# chaprintesting13viasmichael.net
KiCad netlist of a schematic drawn in EAGLE
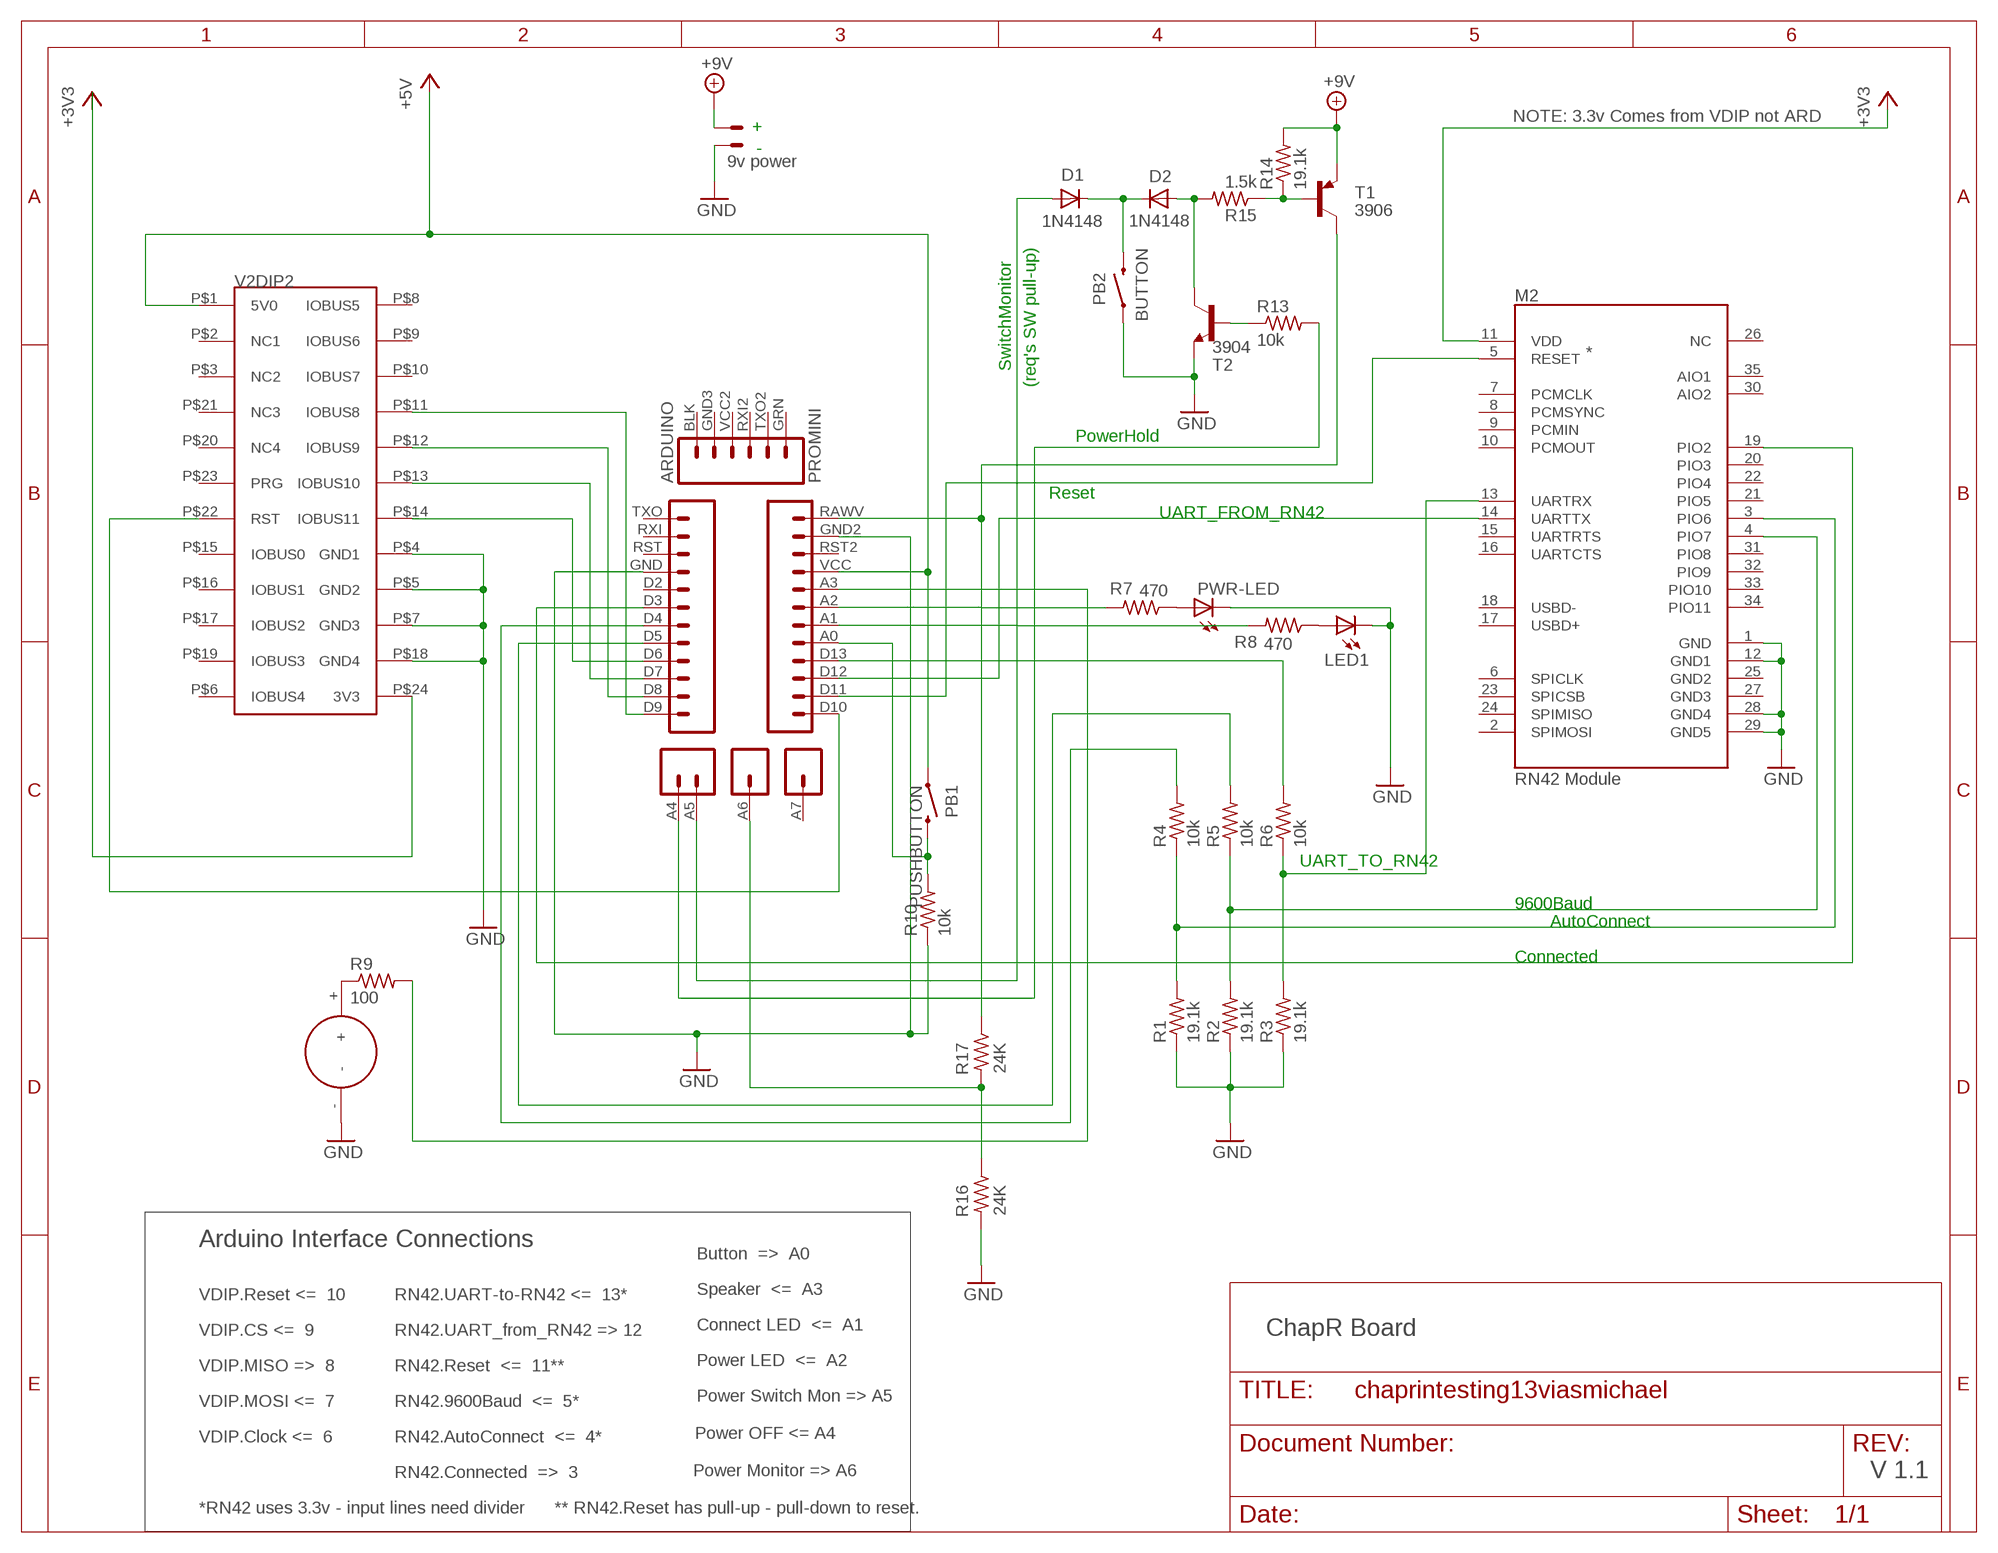
[diagram p0: schematic, sheet 1]

(export (version "E")
  (design (tool "Eeschema 10.0.6"))
  (components
    (comp (ref "-")
      (value "9v power")
      (footprint "eagle-import:22-23-2021")
      (fields (field (name "MF") "MOLEX") (field (name "MPN") "22-23-2021"))
      (libsource (lib "eagle-import") (part "22-23-2021"))
    )
    (comp (ref "ARDUINO")
      (value "PROMINI")
      (footprint "eagle-import:PROMINI")
      (libsource (lib "eagle-import") (part "PROMINI"))
    )
    (comp (ref "D1")
      (value "1N4148")
      (footprint "eagle-import:DO35-7")
      (libsource (lib "eagle-import") (part "1N4148DO35-7"))
    )
    (comp (ref "D2")
      (value "1N4148")
      (footprint "eagle-import:DO35-7")
      (libsource (lib "eagle-import") (part "1N4148DO35-7"))
    )
    (comp (ref "LED1")
      (value "LED3MM")
      (footprint "eagle-import:LED3MM")
      (libsource (lib "eagle-import") (part "LED3MM"))
    )
    (comp (ref "M2")
      (value "RN42 Module")
      (footprint "eagle-import:RN41")
      (libsource (lib "eagle-import") (part "BLUETOOTH-RN41{dblquote}"))
    )
    (comp (ref "PB1")
      (value "PUSHBUTTON")
      (footprint "eagle-import:2-PIN-PUSHBUTTON")
      (libsource (lib "eagle-import") (part "PUSHBUTTON"))
    )
    (comp (ref "PB2")
      (value "BUTTON")
      (footprint "eagle-import:2-PIN-PUSHBUTTON")
      (libsource (lib "eagle-import") (part "PUSHBUTTON"))
    )
    (comp (ref "PWR-LED")
      (value "LED3MM")
      (footprint "eagle-import:LED3MM")
      (libsource (lib "eagle-import") (part "LED3MM"))
    )
    (comp (ref "R1")
      (value "19.1k")
      (footprint "eagle-import:0207_10")
      (libsource (lib "eagle-import") (part "R-US_0207/10"))
    )
    (comp (ref "R2")
      (value "19.1k")
      (footprint "eagle-import:0207_10")
      (libsource (lib "eagle-import") (part "R-US_0207/10"))
    )
    (comp (ref "R3")
      (value "19.1k")
      (footprint "eagle-import:0207_10")
      (libsource (lib "eagle-import") (part "R-US_0207/10"))
    )
    (comp (ref "R4")
      (value "10k")
      (footprint "eagle-import:0207_10")
      (libsource (lib "eagle-import") (part "R-US_0207/10"))
    )
    (comp (ref "R5")
      (value "10k")
      (footprint "eagle-import:0207_10")
      (libsource (lib "eagle-import") (part "R-US_0207/10"))
    )
    (comp (ref "R6")
      (value "10k")
      (footprint "eagle-import:0207_10")
      (libsource (lib "eagle-import") (part "R-US_0207/10"))
    )
    (comp (ref "R7")
      (value "470")
      (footprint "eagle-import:0207_10")
      (libsource (lib "eagle-import") (part "R-US_0207/10"))
    )
    (comp (ref "R8")
      (value "470")
      (footprint "eagle-import:0207_10")
      (libsource (lib "eagle-import") (part "R-US_0207/10"))
    )
    (comp (ref "R9")
      (value "100")
      (footprint "eagle-import:0207_10")
      (libsource (lib "eagle-import") (part "R-US_0207/10"))
    )
    (comp (ref "R10")
      (value "10k")
      (footprint "eagle-import:0207_10")
      (libsource (lib "eagle-import") (part "R-US_0207/10"))
    )
    (comp (ref "R13")
      (value "10k")
      (footprint "eagle-import:0207_10")
      (libsource (lib "eagle-import") (part "R-US_0207/10"))
    )
    (comp (ref "R14")
      (value "19.1k")
      (footprint "eagle-import:0207_10")
      (libsource (lib "eagle-import") (part "R-US_0207/10"))
    )
    (comp (ref "R15")
      (value "1.5k")
      (footprint "eagle-import:0207_10")
      (libsource (lib "eagle-import") (part "R-US_0207/10"))
    )
    (comp (ref "R16")
      (value "24K")
      (footprint "eagle-import:0207_10")
      (libsource (lib "eagle-import") (part "R-US_0207/10"))
    )
    (comp (ref "R17")
      (value "24K")
      (footprint "eagle-import:0207_10")
      (libsource (lib "eagle-import") (part "R-US_0207/10"))
    )
    (comp (ref "T1")
      (value "3906")
      (footprint "eagle-import:TO92-EBC")
      (libsource (lib "eagle-import") (part "-PNP-TO92-EBC"))
    )
    (comp (ref "T2")
      (value "3904")
      (footprint "eagle-import:TO92-EBC")
      (libsource (lib "eagle-import") (part "-NPN-TO92-EBC"))
    )
    (comp (ref "U$2")
      (value "SPEAKER")
      (footprint "eagle-import:SPEAKER")
      (libsource (lib "eagle-import") (part "SPEAKER"))
    )
    (comp (ref "V2DIP2")
      (value "V2DIP2")
      (footprint "eagle-import:V2DIP2")
      (libsource (lib "eagle-import") (part "V2DIP2"))
    )
  )
  (nets
    (net (code "1") (name "+3V3") (class "Default")
      (node (ref "M2") (pin "11") (pinfunction "VDD_11") (pintype "bidirectional"))
    )
    (net (code "2") (name "+5V") (class "Default")
      (node (ref "ARDUINO") (pin "VCC") (pinfunction "VCC_VCC") (pintype "passive"))
      (node (ref "PB1") (pin "P$1") (pinfunction "1_P$1") (pintype "passive"))
      (node (ref "V2DIP2") (pin "P$1") (pinfunction "5V0_P$1") (pintype "bidirectional"))
    )
    (net (code "3") (name "+9V") (class "Default")
      (node (ref "-") (pin "2") (pinfunction "S_2") (pintype "passive"))
      (node (ref "R14") (pin "2") (pinfunction "2_2") (pintype "passive"))
      (node (ref "T1") (pin "E") (pinfunction "E_E") (pintype "passive"))
    )
    (net (code "4") (name "GND") (class "Default")
      (node (ref "-") (pin "1") (pinfunction "S_1") (pintype "passive"))
      (node (ref "ARDUINO") (pin "GND") (pinfunction "GND_GND") (pintype "passive"))
      (node (ref "ARDUINO") (pin "GND2") (pinfunction "GND2_GND2") (pintype "passive"))
      (node (ref "LED1") (pin "K") (pinfunction "C_K") (pintype "passive"))
      (node (ref "M2") (pin "1") (pinfunction "GND_1") (pintype "bidirectional"))
      (node (ref "M2") (pin "12") (pinfunction "GND1_12") (pintype "bidirectional"))
      (node (ref "M2") (pin "28") (pinfunction "GND4_28") (pintype "bidirectional"))
      (node (ref "M2") (pin "29") (pinfunction "GND5_29") (pintype "bidirectional"))
      (node (ref "PB2") (pin "P$1") (pinfunction "1_P$1") (pintype "passive"))
      (node (ref "PWR-LED") (pin "K") (pinfunction "C_K") (pintype "passive"))
      (node (ref "R1") (pin "1") (pinfunction "1_1") (pintype "passive"))
      (node (ref "R10") (pin "1") (pinfunction "1_1") (pintype "passive"))
      (node (ref "R16") (pin "2") (pinfunction "2_2") (pintype "passive"))
      (node (ref "R2") (pin "1") (pinfunction "1_1") (pintype "passive"))
      (node (ref "R3") (pin "1") (pinfunction "1_1") (pintype "passive"))
      (node (ref "T2") (pin "E") (pinfunction "E_E") (pintype "passive"))
      (node (ref "U$2") (pin "-") (pinfunction "-_-") (pintype "bidirectional"))
      (node (ref "V2DIP2") (pin "P$18") (pinfunction "GND4_P$18") (pintype "bidirectional"))
      (node (ref "V2DIP2") (pin "P$4") (pinfunction "GND1_P$4") (pintype "bidirectional"))
      (node (ref "V2DIP2") (pin "P$5") (pinfunction "GND2_P$5") (pintype "bidirectional"))
      (node (ref "V2DIP2") (pin "P$7") (pinfunction "GND3_P$7") (pintype "bidirectional"))
    )
    (net (code "5") (name "Net-(ARDUINO-PadA1)") (class "Default")
      (node (ref "ARDUINO") (pin "A1") (pinfunction "A1_A1") (pintype "passive"))
      (node (ref "R8") (pin "2") (pinfunction "2_2") (pintype "passive"))
    )
    (net (code "6") (name "Net-(ARDUINO-PadA2)") (class "Default")
      (node (ref "ARDUINO") (pin "A2") (pinfunction "A2_A2") (pintype "passive"))
      (node (ref "R7") (pin "2") (pinfunction "2_2") (pintype "passive"))
    )
    (net (code "7") (name "Net-(ARDUINO-PadA3)") (class "Default")
      (node (ref "ARDUINO") (pin "A3") (pinfunction "A3_A3") (pintype "passive"))
      (node (ref "R9") (pin "2") (pinfunction "2_2") (pintype "passive"))
    )
    (net (code "8") (name "Net-(ARDUINO-PadA4)") (class "Default")
      (node (ref "ARDUINO") (pin "A4") (pinfunction "A4_A4") (pintype "passive"))
      (node (ref "R13") (pin "2") (pinfunction "2_2") (pintype "passive"))
    )
    (net (code "9") (name "Net-(ARDUINO-PadA5)") (class "Default")
      (node (ref "ARDUINO") (pin "A5") (pinfunction "A5_A5") (pintype "passive"))
      (node (ref "D1") (pin "A") (pinfunction "A_A") (pintype "passive"))
    )
    (net (code "10") (name "Net-(ARDUINO-PadA6)") (class "Default")
      (node (ref "ARDUINO") (pin "A6") (pinfunction "A6_A6") (pintype "passive"))
      (node (ref "R16") (pin "1") (pinfunction "1_1") (pintype "passive"))
      (node (ref "R17") (pin "2") (pinfunction "2_2") (pintype "passive"))
    )
    (net (code "11") (name "Net-(ARDUINO-PadD4)") (class "Default")
      (node (ref "ARDUINO") (pin "D4") (pinfunction "D4_D4") (pintype "passive"))
      (node (ref "R4") (pin "2") (pinfunction "2_2") (pintype "passive"))
    )
    (net (code "12") (name "Net-(ARDUINO-PadD5)") (class "Default")
      (node (ref "ARDUINO") (pin "D5") (pinfunction "D5_D5") (pintype "passive"))
      (node (ref "R5") (pin "2") (pinfunction "2_2") (pintype "passive"))
    )
    (net (code "13") (name "Net-(ARDUINO-PadD13)") (class "Default")
      (node (ref "ARDUINO") (pin "D13") (pinfunction "D13_D13") (pintype "passive"))
      (node (ref "R6") (pin "2") (pinfunction "2_2") (pintype "passive"))
    )
    (net (code "14") (name "Net-(ARDUINO-PadRAWV)") (class "Default")
      (node (ref "ARDUINO") (pin "RAWV") (pinfunction "RAWV_RAWV") (pintype "passive"))
      (node (ref "R17") (pin "1") (pinfunction "1_1") (pintype "passive"))
      (node (ref "T1") (pin "C") (pinfunction "C_C") (pintype "passive"))
    )
    (net (code "15") (name "Net-(D2-PadA)") (class "Default")
      (node (ref "D2") (pin "A") (pinfunction "A_A") (pintype "passive"))
      (node (ref "R15") (pin "2") (pinfunction "2_2") (pintype "passive"))
      (node (ref "T2") (pin "C") (pinfunction "C_C") (pintype "passive"))
    )
    (net (code "16") (name "Net-(LED1-PadA)") (class "Default")
      (node (ref "LED1") (pin "A") (pinfunction "A_A") (pintype "passive"))
      (node (ref "R8") (pin "1") (pinfunction "1_1") (pintype "passive"))
    )
    (net (code "17") (name "Net-(M2-PIO2)") (class "Default")
      (node (ref "ARDUINO") (pin "D3") (pinfunction "D3_D3") (pintype "passive"))
      (node (ref "M2") (pin "19") (pinfunction "PIO2_19") (pintype "bidirectional"))
    )
    (net (code "18") (name "Net-(M2-PIO6)") (class "Default")
      (node (ref "M2") (pin "3") (pinfunction "PIO6_3") (pintype "bidirectional"))
      (node (ref "R1") (pin "2") (pinfunction "2_2") (pintype "passive"))
      (node (ref "R4") (pin "1") (pinfunction "1_1") (pintype "passive"))
    )
    (net (code "19") (name "Net-(M2-PIO7)") (class "Default")
      (node (ref "M2") (pin "4") (pinfunction "PIO7_4") (pintype "bidirectional"))
      (node (ref "R2") (pin "2") (pinfunction "2_2") (pintype "passive"))
      (node (ref "R5") (pin "1") (pinfunction "1_1") (pintype "passive"))
    )
    (net (code "20") (name "Net-(M2-RESET)") (class "Default")
      (node (ref "ARDUINO") (pin "D11") (pinfunction "D11_D11") (pintype "passive"))
      (node (ref "M2") (pin "5") (pinfunction "RESET_5") (pintype "bidirectional"))
    )
    (net (code "21") (name "Net-(M2-UARTRX)") (class "Default")
      (node (ref "M2") (pin "13") (pinfunction "UARTRX_13") (pintype "bidirectional"))
      (node (ref "R3") (pin "2") (pinfunction "2_2") (pintype "passive"))
      (node (ref "R6") (pin "1") (pinfunction "1_1") (pintype "passive"))
    )
    (net (code "22") (name "Net-(M2-UARTTX)") (class "Default")
      (node (ref "ARDUINO") (pin "D12") (pinfunction "D12_D12") (pintype "passive"))
      (node (ref "M2") (pin "14") (pinfunction "UARTTX_14") (pintype "bidirectional"))
    )
    (net (code "23") (name "Net-(PB1-2)") (class "Default")
      (node (ref "ARDUINO") (pin "A0") (pinfunction "A0_A0") (pintype "passive"))
      (node (ref "PB1") (pin "P$2") (pinfunction "2_P$2") (pintype "passive"))
      (node (ref "R10") (pin "2") (pinfunction "2_2") (pintype "passive"))
    )
    (net (code "24") (name "Net-(PB2-2)") (class "Default")
      (node (ref "D1") (pin "C") (pinfunction "C_C") (pintype "passive"))
      (node (ref "D2") (pin "C") (pinfunction "C_C") (pintype "passive"))
      (node (ref "PB2") (pin "P$2") (pinfunction "2_P$2") (pintype "passive"))
    )
    (net (code "25") (name "Net-(PWR-LED-PadA)") (class "Default")
      (node (ref "PWR-LED") (pin "A") (pinfunction "A_A") (pintype "passive"))
      (node (ref "R7") (pin "1") (pinfunction "1_1") (pintype "passive"))
    )
    (net (code "26") (name "Net-(R9-Pad1)") (class "Default")
      (node (ref "R9") (pin "1") (pinfunction "1_1") (pintype "passive"))
      (node (ref "U$2") (pin "+") (pinfunction "+_+") (pintype "bidirectional"))
    )
    (net (code "27") (name "Net-(R13-Pad1)") (class "Default")
      (node (ref "R13") (pin "1") (pinfunction "1_1") (pintype "passive"))
      (node (ref "T2") (pin "B") (pinfunction "B_B") (pintype "passive"))
    )
    (net (code "28") (name "Net-(R14-Pad1)") (class "Default")
      (node (ref "R14") (pin "1") (pinfunction "1_1") (pintype "passive"))
      (node (ref "R15") (pin "1") (pinfunction "1_1") (pintype "passive"))
      (node (ref "T1") (pin "B") (pinfunction "B_B") (pintype "passive"))
    )
    (net (code "29") (name "Net-(V2DIP2-IOBUS8)") (class "Default")
      (node (ref "ARDUINO") (pin "D9") (pinfunction "D9_D9") (pintype "passive"))
      (node (ref "V2DIP2") (pin "P$11") (pinfunction "IOBUS8_P$11") (pintype "bidirectional"))
    )
    (net (code "30") (name "Net-(V2DIP2-IOBUS9)") (class "Default")
      (node (ref "ARDUINO") (pin "D8") (pinfunction "D8_D8") (pintype "passive"))
      (node (ref "V2DIP2") (pin "P$12") (pinfunction "IOBUS9_P$12") (pintype "bidirectional"))
    )
    (net (code "31") (name "Net-(V2DIP2-IOBUS10)") (class "Default")
      (node (ref "ARDUINO") (pin "D7") (pinfunction "D7_D7") (pintype "passive"))
      (node (ref "V2DIP2") (pin "P$13") (pinfunction "IOBUS10_P$13") (pintype "bidirectional"))
    )
    (net (code "32") (name "Net-(V2DIP2-IOBUS11)") (class "Default")
      (node (ref "ARDUINO") (pin "D6") (pinfunction "D6_D6") (pintype "passive"))
      (node (ref "V2DIP2") (pin "P$14") (pinfunction "IOBUS11_P$14") (pintype "bidirectional"))
    )
    (net (code "33") (name "Net-(V2DIP2-RST)") (class "Default")
      (node (ref "ARDUINO") (pin "D10") (pinfunction "D10_D10") (pintype "passive"))
      (node (ref "V2DIP2") (pin "P$22") (pinfunction "RST_P$22") (pintype "bidirectional"))
    )
    (net (code "34") (name "unconnected-(ARDUINO-PadA7)") (class "Default")
      (node (ref "ARDUINO") (pin "A7") (pinfunction "A7_A7") (pintype "passive"))
    )
    (net (code "35") (name "unconnected-(ARDUINO-PadBLK)") (class "Default")
      (node (ref "ARDUINO") (pin "BLK") (pinfunction "BLK_BLK") (pintype "passive"))
    )
    (net (code "36") (name "unconnected-(ARDUINO-PadD2)") (class "Default")
      (node (ref "ARDUINO") (pin "D2") (pinfunction "D2_D2") (pintype "passive"))
    )
    (net (code "37") (name "unconnected-(ARDUINO-PadGND3)") (class "Default")
      (node (ref "ARDUINO") (pin "GND3") (pinfunction "GND3_GND3") (pintype "passive"))
    )
    (net (code "38") (name "unconnected-(ARDUINO-PadGRN)") (class "Default")
      (node (ref "ARDUINO") (pin "GRN") (pinfunction "GRN_GRN") (pintype "passive"))
    )
    (net (code "39") (name "unconnected-(ARDUINO-PadRST)") (class "Default")
      (node (ref "ARDUINO") (pin "RST") (pinfunction "RST_RST") (pintype "passive"))
    )
    (net (code "40") (name "unconnected-(ARDUINO-PadRST2)") (class "Default")
      (node (ref "ARDUINO") (pin "RST2") (pinfunction "RST2_RST2") (pintype "passive"))
    )
    (net (code "41") (name "unconnected-(ARDUINO-PadRXI)") (class "Default")
      (node (ref "ARDUINO") (pin "RXI") (pinfunction "RXI_RXI") (pintype "passive"))
    )
    (net (code "42") (name "unconnected-(ARDUINO-PadRXI2)") (class "Default")
      (node (ref "ARDUINO") (pin "RXI2") (pinfunction "RXI2_RXI2") (pintype "passive"))
    )
    (net (code "43") (name "unconnected-(ARDUINO-PadTXO)") (class "Default")
      (node (ref "ARDUINO") (pin "TXO") (pinfunction "TXO_TXO") (pintype "passive"))
    )
    (net (code "44") (name "unconnected-(ARDUINO-PadTXO2)") (class "Default")
      (node (ref "ARDUINO") (pin "TXO2") (pinfunction "TXO2_TXO2") (pintype "passive"))
    )
    (net (code "45") (name "unconnected-(ARDUINO-PadVCC2)") (class "Default")
      (node (ref "ARDUINO") (pin "VCC2") (pinfunction "VCC2_VCC2") (pintype "passive"))
    )
    (net (code "46") (name "unconnected-(M2-AIO1-Pad35)") (class "Default")
      (node (ref "M2") (pin "35") (pinfunction "AIO1_35") (pintype "bidirectional"))
    )
    (net (code "47") (name "unconnected-(M2-AIO2-Pad30)") (class "Default")
      (node (ref "M2") (pin "30") (pinfunction "AIO2_30") (pintype "bidirectional"))
    )
    (net (code "48") (name "unconnected-(M2-GND2-Pad25)") (class "Default")
      (node (ref "M2") (pin "25") (pinfunction "GND2_25") (pintype "bidirectional"))
    )
    (net (code "49") (name "unconnected-(M2-GND3-Pad27)") (class "Default")
      (node (ref "M2") (pin "27") (pinfunction "GND3_27") (pintype "bidirectional"))
    )
    (net (code "50") (name "unconnected-(M2-NC-Pad26)") (class "Default")
      (node (ref "M2") (pin "26") (pinfunction "NC_26") (pintype "bidirectional"))
    )
    (net (code "51") (name "unconnected-(M2-PCMCLK-Pad7)") (class "Default")
      (node (ref "M2") (pin "7") (pinfunction "PCMCLK_7") (pintype "bidirectional"))
    )
    (net (code "52") (name "unconnected-(M2-PCMIN-Pad9)") (class "Default")
      (node (ref "M2") (pin "9") (pinfunction "PCMIN_9") (pintype "bidirectional"))
    )
    (net (code "53") (name "unconnected-(M2-PCMOUT-Pad10)") (class "Default")
      (node (ref "M2") (pin "10") (pinfunction "PCMOUT_10") (pintype "bidirectional"))
    )
    (net (code "54") (name "unconnected-(M2-PCMSYNC-Pad8)") (class "Default")
      (node (ref "M2") (pin "8") (pinfunction "PCMSYNC_8") (pintype "bidirectional"))
    )
    (net (code "55") (name "unconnected-(M2-PIO3-Pad20)") (class "Default")
      (node (ref "M2") (pin "20") (pinfunction "PIO3_20") (pintype "bidirectional"))
    )
    (net (code "56") (name "unconnected-(M2-PIO4-Pad22)") (class "Default")
      (node (ref "M2") (pin "22") (pinfunction "PIO4_22") (pintype "bidirectional"))
    )
    (net (code "57") (name "unconnected-(M2-PIO5-Pad21)") (class "Default")
      (node (ref "M2") (pin "21") (pinfunction "PIO5_21") (pintype "bidirectional"))
    )
    (net (code "58") (name "unconnected-(M2-PIO8-Pad31)") (class "Default")
      (node (ref "M2") (pin "31") (pinfunction "PIO8_31") (pintype "bidirectional"))
    )
    (net (code "59") (name "unconnected-(M2-PIO9-Pad32)") (class "Default")
      (node (ref "M2") (pin "32") (pinfunction "PIO9_32") (pintype "bidirectional"))
    )
    (net (code "60") (name "unconnected-(M2-PIO10-Pad33)") (class "Default")
      (node (ref "M2") (pin "33") (pinfunction "PIO10_33") (pintype "bidirectional"))
    )
    (net (code "61") (name "unconnected-(M2-PIO11-Pad34)") (class "Default")
      (node (ref "M2") (pin "34") (pinfunction "PIO11_34") (pintype "bidirectional"))
    )
    (net (code "62") (name "unconnected-(M2-SPICLK-Pad6)") (class "Default")
      (node (ref "M2") (pin "6") (pinfunction "SPICLK_6") (pintype "bidirectional"))
    )
    (net (code "63") (name "unconnected-(M2-SPICSB-Pad23)") (class "Default")
      (node (ref "M2") (pin "23") (pinfunction "SPICSB_23") (pintype "bidirectional"))
    )
    (net (code "64") (name "unconnected-(M2-SPIMISO-Pad24)") (class "Default")
      (node (ref "M2") (pin "24") (pinfunction "SPIMISO_24") (pintype "bidirectional"))
    )
    (net (code "65") (name "unconnected-(M2-SPIMOSI-Pad2)") (class "Default")
      (node (ref "M2") (pin "2") (pinfunction "SPIMOSI_2") (pintype "bidirectional"))
    )
    (net (code "66") (name "unconnected-(M2-UARTCTS-Pad16)") (class "Default")
      (node (ref "M2") (pin "16") (pinfunction "UARTCTS_16") (pintype "bidirectional"))
    )
    (net (code "67") (name "unconnected-(M2-UARTRTS-Pad15)") (class "Default")
      (node (ref "M2") (pin "15") (pinfunction "UARTRTS_15") (pintype "bidirectional"))
    )
    (net (code "68") (name "unconnected-(M2-USBD+-Pad17)") (class "Default")
      (node (ref "M2") (pin "17") (pinfunction "USBD+_17") (pintype "bidirectional"))
    )
    (net (code "69") (name "unconnected-(M2-USBD--Pad18)") (class "Default")
      (node (ref "M2") (pin "18") (pinfunction "USBD-_18") (pintype "bidirectional"))
    )
    (net (code "70") (name "unconnected-(V2DIP2-3V3-PadP$24)") (class "Default")
      (node (ref "V2DIP2") (pin "P$24") (pinfunction "3V3_P$24") (pintype "bidirectional"))
    )
    (net (code "71") (name "unconnected-(V2DIP2-IOBUS0-PadP$15)") (class "Default")
      (node (ref "V2DIP2") (pin "P$15") (pinfunction "IOBUS0_P$15") (pintype "bidirectional"))
    )
    (net (code "72") (name "unconnected-(V2DIP2-IOBUS1-PadP$16)") (class "Default")
      (node (ref "V2DIP2") (pin "P$16") (pinfunction "IOBUS1_P$16") (pintype "bidirectional"))
    )
    (net (code "73") (name "unconnected-(V2DIP2-IOBUS2-PadP$17)") (class "Default")
      (node (ref "V2DIP2") (pin "P$17") (pinfunction "IOBUS2_P$17") (pintype "bidirectional"))
    )
    (net (code "74") (name "unconnected-(V2DIP2-IOBUS3-PadP$19)") (class "Default")
      (node (ref "V2DIP2") (pin "P$19") (pinfunction "IOBUS3_P$19") (pintype "bidirectional"))
    )
    (net (code "75") (name "unconnected-(V2DIP2-IOBUS4-PadP$6)") (class "Default")
      (node (ref "V2DIP2") (pin "P$6") (pinfunction "IOBUS4_P$6") (pintype "bidirectional"))
    )
    (net (code "76") (name "unconnected-(V2DIP2-IOBUS5-PadP$8)") (class "Default")
      (node (ref "V2DIP2") (pin "P$8") (pinfunction "IOBUS5_P$8") (pintype "bidirectional"))
    )
    (net (code "77") (name "unconnected-(V2DIP2-IOBUS6-PadP$9)") (class "Default")
      (node (ref "V2DIP2") (pin "P$9") (pinfunction "IOBUS6_P$9") (pintype "bidirectional"))
    )
    (net (code "78") (name "unconnected-(V2DIP2-IOBUS7-PadP$10)") (class "Default")
      (node (ref "V2DIP2") (pin "P$10") (pinfunction "IOBUS7_P$10") (pintype "bidirectional"))
    )
    (net (code "79") (name "unconnected-(V2DIP2-NC1-PadP$2)") (class "Default")
      (node (ref "V2DIP2") (pin "P$2") (pinfunction "NC1_P$2") (pintype "bidirectional"))
    )
    (net (code "80") (name "unconnected-(V2DIP2-NC2-PadP$3)") (class "Default")
      (node (ref "V2DIP2") (pin "P$3") (pinfunction "NC2_P$3") (pintype "bidirectional"))
    )
    (net (code "81") (name "unconnected-(V2DIP2-NC3-PadP$21)") (class "Default")
      (node (ref "V2DIP2") (pin "P$21") (pinfunction "NC3_P$21") (pintype "bidirectional"))
    )
    (net (code "82") (name "unconnected-(V2DIP2-NC4-PadP$20)") (class "Default")
      (node (ref "V2DIP2") (pin "P$20") (pinfunction "NC4_P$20") (pintype "bidirectional"))
    )
    (net (code "83") (name "unconnected-(V2DIP2-PRG-PadP$23)") (class "Default")
      (node (ref "V2DIP2") (pin "P$23") (pinfunction "PRG_P$23") (pintype "bidirectional"))
    )
  )
)
